# Nexus_links_pcb1.net
KiCad netlist of a schematic drawn in EAGLE
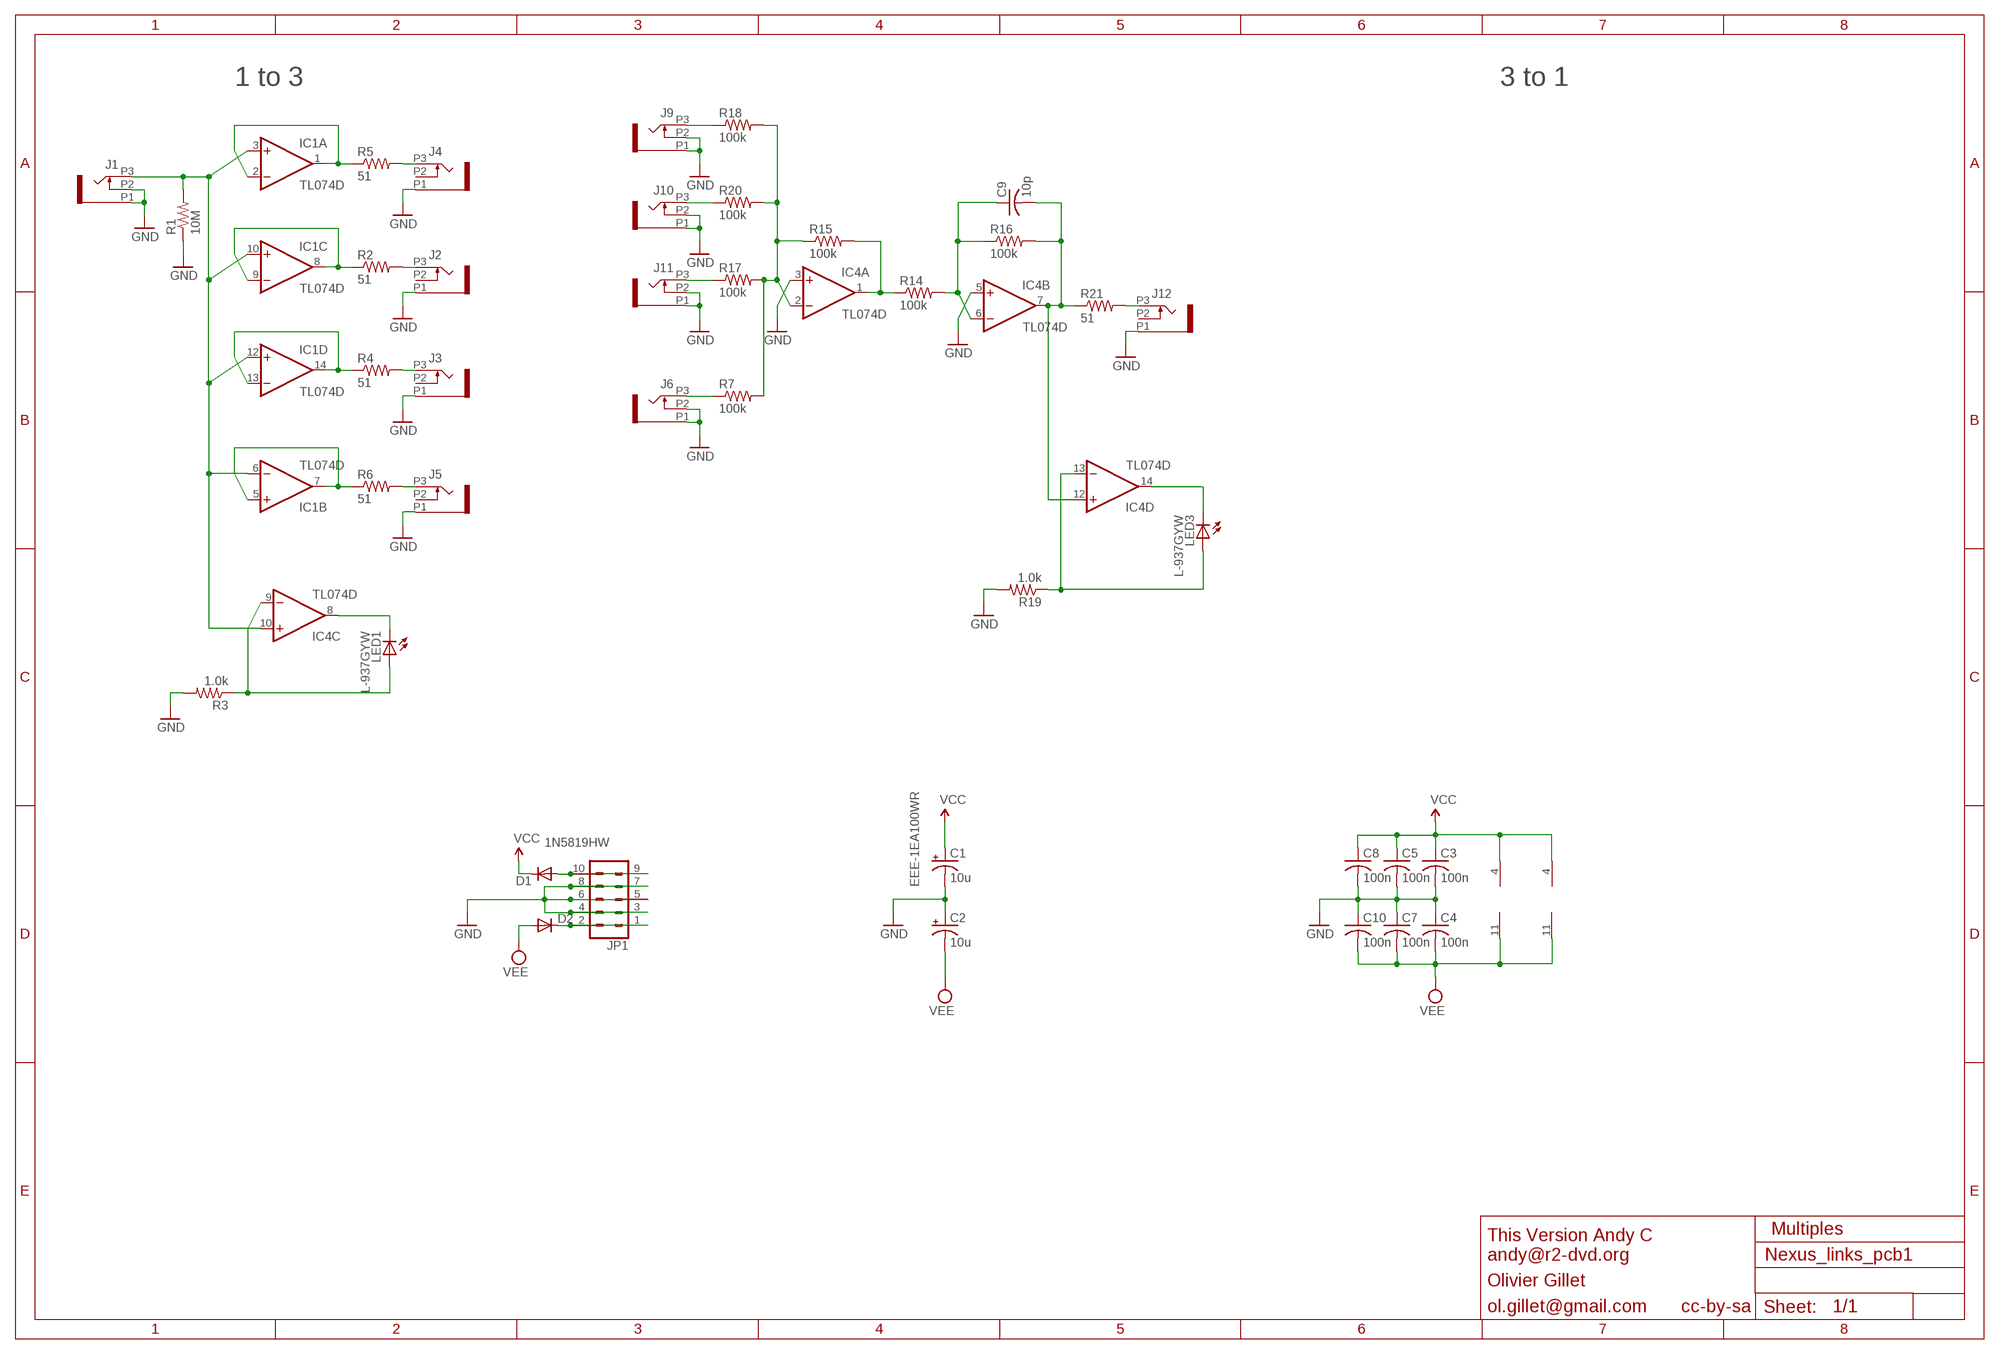
[diagram p0: schematic, sheet 1]

(export (version "E")
  (design (tool "Eeschema 10.0.6"))
  (components
    (comp (ref "C1")
      (value "10u")
      (footprint "eagle-import:PANASONIC_A")
      (fields (field (name "RSPARTNUMBER") "568-711"))
      (libsource (lib "eagle-import") (part "CPOL-USA"))
    )
    (comp (ref "C2")
      (value "10u")
      (footprint "eagle-import:PANASONIC_A")
      (fields (field (name "RSPARTNUMBER") "568-711"))
      (libsource (lib "eagle-import") (part "CPOL-USA"))
    )
    (comp (ref "C3")
      (value "100n")
      (footprint "eagle-import:C0603")
      (fields (field (name "RSPARTNUMBER") "264-4416"))
      (libsource (lib "eagle-import") (part "C-USC0603"))
    )
    (comp (ref "C4")
      (value "100n")
      (footprint "eagle-import:C0603")
      (libsource (lib "eagle-import") (part "C-USC0603"))
    )
    (comp (ref "C5")
      (value "100n")
      (footprint "eagle-import:C0603")
      (libsource (lib "eagle-import") (part "C-USC0603"))
    )
    (comp (ref "C7")
      (value "100n")
      (footprint "eagle-import:C0603")
      (libsource (lib "eagle-import") (part "C-USC0603"))
    )
    (comp (ref "C8")
      (value "100n")
      (footprint "eagle-import:C0603")
      (libsource (lib "eagle-import") (part "C-USC0603"))
    )
    (comp (ref "C9")
      (value "10p")
      (footprint "eagle-import:C0603")
      (fields (field (name "RSPARTNUMBER") "601-0198 "))
      (libsource (lib "eagle-import") (part "C-USC0603"))
    )
    (comp (ref "C10")
      (value "100n")
      (footprint "eagle-import:C0603")
      (libsource (lib "eagle-import") (part "C-USC0603"))
    )
    (comp (ref "D1")
      (value "1N5819HW")
      (footprint "eagle-import:SOD123")
      (fields (field (name "RSPARTNUMBER") "708-2197"))
      (libsource (lib "eagle-import") (part "DIODE-SOD123"))
    )
    (comp (ref "D2")
      (value "1N5819HW")
      (footprint "eagle-import:SOD123")
      (fields (field (name "RSPARTNUMBER") "708-2197"))
      (libsource (lib "eagle-import") (part "DIODE-SOD123"))
    )
    (comp (ref "IC1")
      (value "TL074D")
      (footprint "eagle-import:SO14")
      (fields (field (name "RSPARTNUMBER") "661-0076"))
      (libsource (lib "eagle-import") (part "TL074D"))
    )
    (comp (ref "IC4")
      (value "TL074D")
      (footprint "eagle-import:SO14")
      (libsource (lib "eagle-import") (part "TL074D"))
    )
    (comp (ref "J1")
      (value "PJ301_THONKICONN6")
      (footprint "eagle-import:WQP_PJ_301M6")
      (libsource (lib "eagle-import") (part "PJ301_THONKICONN6"))
    )
    (comp (ref "J2")
      (value "PJ301_THONKICONN6")
      (footprint "eagle-import:WQP_PJ_301M6")
      (libsource (lib "eagle-import") (part "PJ301_THONKICONN6"))
    )
    (comp (ref "J3")
      (value "PJ301_THONKICONN6")
      (footprint "eagle-import:WQP_PJ_301M6")
      (libsource (lib "eagle-import") (part "PJ301_THONKICONN6"))
    )
    (comp (ref "J4")
      (value "PJ301_THONKICONN6")
      (footprint "eagle-import:WQP_PJ_301M6")
      (libsource (lib "eagle-import") (part "PJ301_THONKICONN6"))
    )
    (comp (ref "J5")
      (value "PJ301_THONKICONN6")
      (footprint "eagle-import:WQP_PJ_301M6")
      (libsource (lib "eagle-import") (part "PJ301_THONKICONN6"))
    )
    (comp (ref "J6")
      (value "PJ301_THONKICONN6")
      (footprint "eagle-import:WQP_PJ_301M6")
      (libsource (lib "eagle-import") (part "PJ301_THONKICONN6"))
    )
    (comp (ref "J9")
      (value "PJ301_THONKICONN6")
      (footprint "eagle-import:WQP_PJ_301M6")
      (libsource (lib "eagle-import") (part "PJ301_THONKICONN6"))
    )
    (comp (ref "J10")
      (value "PJ301_THONKICONN6")
      (footprint "eagle-import:WQP_PJ_301M6")
      (libsource (lib "eagle-import") (part "PJ301_THONKICONN6"))
    )
    (comp (ref "J11")
      (value "PJ301_THONKICONN6")
      (footprint "eagle-import:WQP_PJ_301M6")
      (libsource (lib "eagle-import") (part "PJ301_THONKICONN6"))
    )
    (comp (ref "J12")
      (value "PJ301_THONKICONN6")
      (footprint "eagle-import:WQP_PJ_301M6")
      (libsource (lib "eagle-import") (part "PJ301_THONKICONN6"))
    )
    (comp (ref "JP1")
      (value "CONN_05X2SHD")
      (footprint "eagle-import:2X5-SHROUDED")
      (libsource (lib "eagle-import") (part "CONN_05X2SHD"))
    )
    (comp (ref "LED1")
      (value "L-937GYW")
      (footprint "eagle-import:LED3MM")
      (fields (field (name "RSPARTNUMBER") "228-5663 "))
      (libsource (lib "eagle-import") (part "LED3MM"))
    )
    (comp (ref "LED3")
      (value "L-937GYW")
      (footprint "eagle-import:LED3MM")
      (fields (field (name "RSPARTNUMBER") "228-5663 "))
      (libsource (lib "eagle-import") (part "LED3MM"))
    )
    (comp (ref "R1")
      (value "10M")
      (footprint "eagle-import:R0603")
      (libsource (lib "eagle-import") (part "R-US_R0603"))
    )
    (comp (ref "R2")
      (value "51")
      (footprint "eagle-import:R0603")
      (libsource (lib "eagle-import") (part "R-US_R0603"))
    )
    (comp (ref "R3")
      (value "1.0k")
      (footprint "eagle-import:R0603")
      (libsource (lib "eagle-import") (part "R-US_R0603"))
    )
    (comp (ref "R4")
      (value "51")
      (footprint "eagle-import:R0603")
      (libsource (lib "eagle-import") (part "R-US_R0603"))
    )
    (comp (ref "R5")
      (value "51")
      (footprint "eagle-import:R0603")
      (libsource (lib "eagle-import") (part "R-US_R0603"))
    )
    (comp (ref "R6")
      (value "51")
      (footprint "eagle-import:R0603")
      (libsource (lib "eagle-import") (part "R-US_R0603"))
    )
    (comp (ref "R7")
      (value "100k")
      (footprint "eagle-import:R0603")
      (libsource (lib "eagle-import") (part "R-US_R0603"))
    )
    (comp (ref "R14")
      (value "100k")
      (footprint "eagle-import:R0603")
      (libsource (lib "eagle-import") (part "R-US_R0603"))
    )
    (comp (ref "R15")
      (value "100k")
      (footprint "eagle-import:R0603")
      (libsource (lib "eagle-import") (part "R-US_R0603"))
    )
    (comp (ref "R16")
      (value "100k")
      (footprint "eagle-import:R0603")
      (libsource (lib "eagle-import") (part "R-US_R0603"))
    )
    (comp (ref "R17")
      (value "100k")
      (footprint "eagle-import:R0603")
      (libsource (lib "eagle-import") (part "R-US_R0603"))
    )
    (comp (ref "R18")
      (value "100k")
      (footprint "eagle-import:R0603")
      (libsource (lib "eagle-import") (part "R-US_R0603"))
    )
    (comp (ref "R19")
      (value "1.0k")
      (footprint "eagle-import:R0603")
      (libsource (lib "eagle-import") (part "R-US_R0603"))
    )
    (comp (ref "R20")
      (value "100k")
      (footprint "eagle-import:R0603")
      (libsource (lib "eagle-import") (part "R-US_R0603"))
    )
    (comp (ref "R21")
      (value "51")
      (footprint "eagle-import:R0603")
      (libsource (lib "eagle-import") (part "R-US_R0603"))
    )
  )
  (nets
    (net (code "1") (name "GND") (class "Default")
      (node (ref "C1") (pin "-") (pinfunction "-_-") (pintype "passive"))
      (node (ref "C10") (pin "1") (pinfunction "1_1") (pintype "passive"))
      (node (ref "C2") (pin "+") (pinfunction "+_+") (pintype "passive"))
      (node (ref "C3") (pin "2") (pinfunction "2_2") (pintype "passive"))
      (node (ref "C4") (pin "1") (pinfunction "1_1") (pintype "passive"))
      (node (ref "C5") (pin "2") (pinfunction "2_2") (pintype "passive"))
      (node (ref "C7") (pin "1") (pinfunction "1_1") (pintype "passive"))
      (node (ref "C8") (pin "2") (pinfunction "2_2") (pintype "passive"))
      (node (ref "IC4") (pin "3") (pinfunction "+IN_3") (pintype "input"))
      (node (ref "IC4") (pin "5") (pinfunction "+IN_5") (pintype "input"))
      (node (ref "J1") (pin "P1") (pinfunction "1_P1") (pintype "passive"))
      (node (ref "J1") (pin "P2") (pinfunction "2_P2") (pintype "passive"))
      (node (ref "J10") (pin "P1") (pinfunction "1_P1") (pintype "passive"))
      (node (ref "J10") (pin "P2") (pinfunction "2_P2") (pintype "passive"))
      (node (ref "J11") (pin "P1") (pinfunction "1_P1") (pintype "passive"))
      (node (ref "J11") (pin "P2") (pinfunction "2_P2") (pintype "passive"))
      (node (ref "J12") (pin "P1") (pinfunction "1_P1") (pintype "passive"))
      (node (ref "J2") (pin "P1") (pinfunction "1_P1") (pintype "passive"))
      (node (ref "J3") (pin "P1") (pinfunction "1_P1") (pintype "passive"))
      (node (ref "J4") (pin "P1") (pinfunction "1_P1") (pintype "passive"))
      (node (ref "J5") (pin "P1") (pinfunction "1_P1") (pintype "passive"))
      (node (ref "J6") (pin "P1") (pinfunction "1_P1") (pintype "passive"))
      (node (ref "J6") (pin "P2") (pinfunction "2_P2") (pintype "passive"))
      (node (ref "J9") (pin "P1") (pinfunction "1_P1") (pintype "passive"))
      (node (ref "J9") (pin "P2") (pinfunction "2_P2") (pintype "passive"))
      (node (ref "JP1") (pin "3") (pinfunction "3_3") (pintype "passive"))
      (node (ref "JP1") (pin "4") (pinfunction "4_4") (pintype "passive"))
      (node (ref "JP1") (pin "5") (pinfunction "5_5") (pintype "passive"))
      (node (ref "JP1") (pin "6") (pinfunction "6_6") (pintype "passive"))
      (node (ref "JP1") (pin "7") (pinfunction "7_7") (pintype "passive"))
      (node (ref "JP1") (pin "8") (pinfunction "8_8") (pintype "passive"))
      (node (ref "R1") (pin "1") (pinfunction "1_1") (pintype "passive"))
      (node (ref "R19") (pin "2") (pinfunction "2_2") (pintype "passive"))
      (node (ref "R3") (pin "2") (pinfunction "2_2") (pintype "passive"))
    )
    (net (code "2") (name "Net-(D1-PadA)") (class "Default")
      (node (ref "D1") (pin "A") (pinfunction "A_A") (pintype "passive"))
      (node (ref "JP1") (pin "10") (pinfunction "10_10") (pintype "passive"))
      (node (ref "JP1") (pin "9") (pinfunction "9_9") (pintype "passive"))
    )
    (net (code "3") (name "Net-(D2-PadC)") (class "Default")
      (node (ref "D2") (pin "C") (pinfunction "C_C") (pintype "passive"))
      (node (ref "JP1") (pin "1") (pinfunction "1_1") (pintype "passive"))
      (node (ref "JP1") (pin "2") (pinfunction "2_2") (pintype "passive"))
    )
    (net (code "4") (name "Net-(IC1A-+IN)") (class "Default")
      (node (ref "IC1") (pin "10") (pinfunction "+IN_10") (pintype "input"))
      (node (ref "IC1") (pin "12") (pinfunction "+IN_12") (pintype "input"))
      (node (ref "IC1") (pin "3") (pinfunction "+IN_3") (pintype "input"))
      (node (ref "IC1") (pin "6") (pinfunction "-IN_6") (pintype "input"))
      (node (ref "IC4") (pin "10") (pinfunction "+IN_10") (pintype "input"))
      (node (ref "J1") (pin "P3") (pinfunction "3_P3") (pintype "passive"))
      (node (ref "R1") (pin "2") (pinfunction "2_2") (pintype "passive"))
    )
    (net (code "5") (name "Net-(IC1A--IN)") (class "Default")
      (node (ref "IC1") (pin "1") (pinfunction "OUT_1") (pintype "output"))
      (node (ref "IC1") (pin "2") (pinfunction "-IN_2") (pintype "input"))
      (node (ref "R5") (pin "1") (pinfunction "1_1") (pintype "passive"))
    )
    (net (code "6") (name "Net-(IC1B-+IN)") (class "Default")
      (node (ref "IC1") (pin "5") (pinfunction "+IN_5") (pintype "input"))
      (node (ref "IC1") (pin "7") (pinfunction "OUT_7") (pintype "output"))
      (node (ref "R6") (pin "1") (pinfunction "1_1") (pintype "passive"))
    )
    (net (code "7") (name "Net-(IC1C--IN)") (class "Default")
      (node (ref "IC1") (pin "8") (pinfunction "OUT_8") (pintype "output"))
      (node (ref "IC1") (pin "9") (pinfunction "-IN_9") (pintype "input"))
      (node (ref "R2") (pin "1") (pinfunction "1_1") (pintype "passive"))
    )
    (net (code "8") (name "Net-(IC1D--IN)") (class "Default")
      (node (ref "IC1") (pin "13") (pinfunction "-IN_13") (pintype "input"))
      (node (ref "IC1") (pin "14") (pinfunction "OUT_14") (pintype "output"))
      (node (ref "R4") (pin "1") (pinfunction "1_1") (pintype "passive"))
    )
    (net (code "9") (name "Net-(IC4A--IN)") (class "Default")
      (node (ref "IC4") (pin "2") (pinfunction "-IN_2") (pintype "input"))
      (node (ref "R15") (pin "1") (pinfunction "1_1") (pintype "passive"))
      (node (ref "R17") (pin "2") (pinfunction "2_2") (pintype "passive"))
      (node (ref "R18") (pin "2") (pinfunction "2_2") (pintype "passive"))
      (node (ref "R20") (pin "2") (pinfunction "2_2") (pintype "passive"))
      (node (ref "R7") (pin "2") (pinfunction "2_2") (pintype "passive"))
    )
    (net (code "10") (name "Net-(IC4A-OUT)") (class "Default")
      (node (ref "IC4") (pin "1") (pinfunction "OUT_1") (pintype "output"))
      (node (ref "R14") (pin "1") (pinfunction "1_1") (pintype "passive"))
      (node (ref "R15") (pin "2") (pinfunction "2_2") (pintype "passive"))
    )
    (net (code "11") (name "Net-(IC4B--IN)") (class "Default")
      (node (ref "C9") (pin "1") (pinfunction "1_1") (pintype "passive"))
      (node (ref "IC4") (pin "6") (pinfunction "-IN_6") (pintype "input"))
      (node (ref "R14") (pin "2") (pinfunction "2_2") (pintype "passive"))
      (node (ref "R16") (pin "1") (pinfunction "1_1") (pintype "passive"))
    )
    (net (code "12") (name "Net-(IC4B-OUT)") (class "Default")
      (node (ref "C9") (pin "2") (pinfunction "2_2") (pintype "passive"))
      (node (ref "IC4") (pin "12") (pinfunction "+IN_12") (pintype "input"))
      (node (ref "IC4") (pin "7") (pinfunction "OUT_7") (pintype "output"))
      (node (ref "R16") (pin "2") (pinfunction "2_2") (pintype "passive"))
      (node (ref "R21") (pin "1") (pinfunction "1_1") (pintype "passive"))
    )
    (net (code "13") (name "Net-(IC4C--IN)") (class "Default")
      (node (ref "IC4") (pin "9") (pinfunction "-IN_9") (pintype "input"))
      (node (ref "LED1") (pin "A") (pinfunction "A_A") (pintype "passive"))
      (node (ref "R3") (pin "1") (pinfunction "1_1") (pintype "passive"))
    )
    (net (code "14") (name "Net-(IC4C-OUT)") (class "Default")
      (node (ref "IC4") (pin "8") (pinfunction "OUT_8") (pintype "output"))
      (node (ref "LED1") (pin "K") (pinfunction "C_K") (pintype "passive"))
    )
    (net (code "15") (name "Net-(IC4D--IN)") (class "Default")
      (node (ref "IC4") (pin "13") (pinfunction "-IN_13") (pintype "input"))
      (node (ref "LED3") (pin "A") (pinfunction "A_A") (pintype "passive"))
      (node (ref "R19") (pin "1") (pinfunction "1_1") (pintype "passive"))
    )
    (net (code "16") (name "Net-(IC4D-OUT)") (class "Default")
      (node (ref "IC4") (pin "14") (pinfunction "OUT_14") (pintype "output"))
      (node (ref "LED3") (pin "K") (pinfunction "C_K") (pintype "passive"))
    )
    (net (code "17") (name "Net-(J2-3)") (class "Default")
      (node (ref "J2") (pin "P3") (pinfunction "3_P3") (pintype "passive"))
      (node (ref "R2") (pin "2") (pinfunction "2_2") (pintype "passive"))
    )
    (net (code "18") (name "Net-(J3-3)") (class "Default")
      (node (ref "J3") (pin "P3") (pinfunction "3_P3") (pintype "passive"))
      (node (ref "R4") (pin "2") (pinfunction "2_2") (pintype "passive"))
    )
    (net (code "19") (name "Net-(J4-3)") (class "Default")
      (node (ref "J4") (pin "P3") (pinfunction "3_P3") (pintype "passive"))
      (node (ref "R5") (pin "2") (pinfunction "2_2") (pintype "passive"))
    )
    (net (code "20") (name "Net-(J5-3)") (class "Default")
      (node (ref "J5") (pin "P3") (pinfunction "3_P3") (pintype "passive"))
      (node (ref "R6") (pin "2") (pinfunction "2_2") (pintype "passive"))
    )
    (net (code "21") (name "Net-(J6-3)") (class "Default")
      (node (ref "J6") (pin "P3") (pinfunction "3_P3") (pintype "passive"))
      (node (ref "R7") (pin "1") (pinfunction "1_1") (pintype "passive"))
    )
    (net (code "22") (name "Net-(J9-3)") (class "Default")
      (node (ref "J9") (pin "P3") (pinfunction "3_P3") (pintype "passive"))
      (node (ref "R18") (pin "1") (pinfunction "1_1") (pintype "passive"))
    )
    (net (code "23") (name "Net-(J10-3)") (class "Default")
      (node (ref "J10") (pin "P3") (pinfunction "3_P3") (pintype "passive"))
      (node (ref "R20") (pin "1") (pinfunction "1_1") (pintype "passive"))
    )
    (net (code "24") (name "Net-(J11-3)") (class "Default")
      (node (ref "J11") (pin "P3") (pinfunction "3_P3") (pintype "passive"))
      (node (ref "R17") (pin "1") (pinfunction "1_1") (pintype "passive"))
    )
    (net (code "25") (name "Net-(J12-3)") (class "Default")
      (node (ref "J12") (pin "P3") (pinfunction "3_P3") (pintype "passive"))
      (node (ref "R21") (pin "2") (pinfunction "2_2") (pintype "passive"))
    )
    (net (code "26") (name "VCC") (class "Default")
      (node (ref "C1") (pin "+") (pinfunction "+_+") (pintype "passive"))
      (node (ref "C3") (pin "1") (pinfunction "1_1") (pintype "passive"))
      (node (ref "C5") (pin "1") (pinfunction "1_1") (pintype "passive"))
      (node (ref "C8") (pin "1") (pinfunction "1_1") (pintype "passive"))
      (node (ref "D1") (pin "C") (pinfunction "C_C") (pintype "passive"))
      (node (ref "IC1") (pin "4") (pinfunction "V+_4") (pintype "power_in"))
      (node (ref "IC4") (pin "4") (pinfunction "V+_4") (pintype "power_in"))
    )
    (net (code "27") (name "VEE") (class "Default")
      (node (ref "C10") (pin "2") (pinfunction "2_2") (pintype "passive"))
      (node (ref "C2") (pin "-") (pinfunction "-_-") (pintype "passive"))
      (node (ref "C4") (pin "2") (pinfunction "2_2") (pintype "passive"))
      (node (ref "C7") (pin "2") (pinfunction "2_2") (pintype "passive"))
      (node (ref "D2") (pin "A") (pinfunction "A_A") (pintype "passive"))
      (node (ref "IC1") (pin "11") (pinfunction "V-_11") (pintype "power_in"))
      (node (ref "IC4") (pin "11") (pinfunction "V-_11") (pintype "power_in"))
    )
    (net (code "28") (name "unconnected-(J2-2-PadP2)") (class "Default")
      (node (ref "J2") (pin "P2") (pinfunction "2_P2") (pintype "passive"))
    )
    (net (code "29") (name "unconnected-(J3-2-PadP2)") (class "Default")
      (node (ref "J3") (pin "P2") (pinfunction "2_P2") (pintype "passive"))
    )
    (net (code "30") (name "unconnected-(J4-2-PadP2)") (class "Default")
      (node (ref "J4") (pin "P2") (pinfunction "2_P2") (pintype "passive"))
    )
    (net (code "31") (name "unconnected-(J5-2-PadP2)") (class "Default")
      (node (ref "J5") (pin "P2") (pinfunction "2_P2") (pintype "passive"))
    )
    (net (code "32") (name "unconnected-(J12-2-PadP2)") (class "Default")
      (node (ref "J12") (pin "P2") (pinfunction "2_P2") (pintype "passive"))
    )
  )
)
